# PWM_Output.net
KiCad netlist of a schematic drawn in Altium Designer
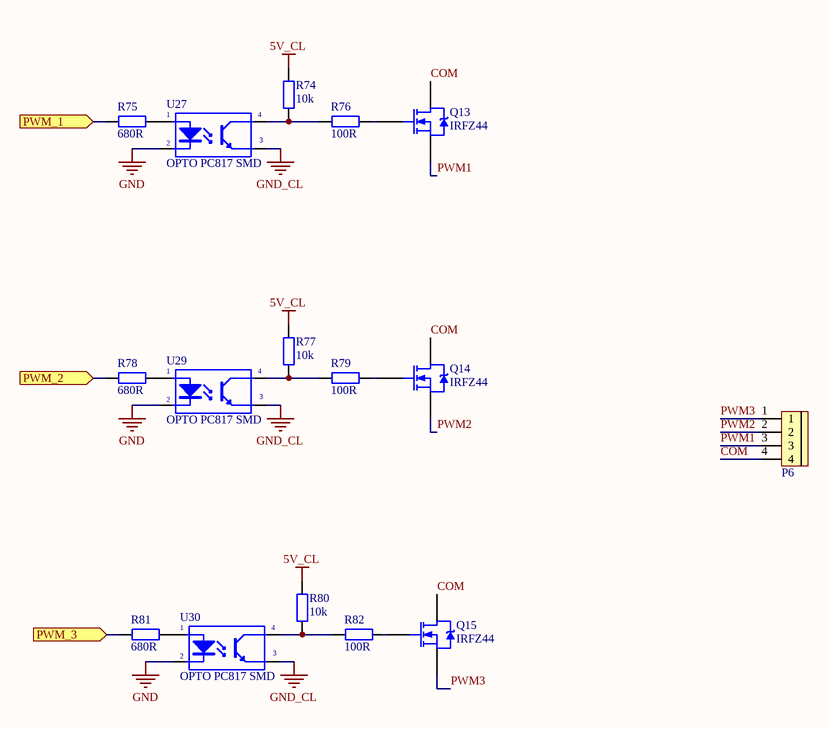
[diagram p0: PWM_Output.SchDoc]

(export (version "E")
  (design (tool "Eeschema 10.0.6"))
  (components
    (comp (ref "P6")
      (value "CON 4 EDG5.08")
      (footprint "CON 4 4EDG5.08")
      (description "Cắm")
      (libsource (lib "Altium_Lib_by_KhueNguyenCreator") (part "CON 4 EDG5.08"))
    )
    (comp (ref "Q13")
      (value "IRFZ44")
      (footprint "TO220")
      (description "N-Channel Power MOSFET")
      (libsource (lib "Altium_Lib_by_KhueNguyenCreator") (part "IRFZ44 DIP"))
    )
    (comp (ref "Q14")
      (value "IRFZ44")
      (footprint "TO220")
      (description "N-Channel Power MOSFET")
      (libsource (lib "Altium_Lib_by_KhueNguyenCreator") (part "IRFZ44 DIP"))
    )
    (comp (ref "Q15")
      (value "IRFZ44")
      (footprint "TO220")
      (description "N-Channel Power MOSFET")
      (libsource (lib "Altium_Lib_by_KhueNguyenCreator") (part "IRFZ44 DIP"))
    )
    (comp (ref "R74")
      (value "10k")
      (footprint "tro smd 0805")
      (description "Dán")
      (libsource (lib "Altium_Lib_by_KhueNguyenCreator") (part "Tro 0805 1% 10k"))
    )
    (comp (ref "R75")
      (value "680R")
      (footprint "tro smd 0805")
      (description "Dán")
      (libsource (lib "Altium_Lib_by_KhueNguyenCreator") (part "Tro 0805 1% 680R"))
    )
    (comp (ref "R76")
      (value "100R")
      (footprint "tro smd 0805")
      (description "Dán")
      (libsource (lib "Altium_Lib_by_KhueNguyenCreator") (part "Tro 0805 5% 100R"))
    )
    (comp (ref "R77")
      (value "10k")
      (footprint "tro smd 0805")
      (description "Dán")
      (libsource (lib "Altium_Lib_by_KhueNguyenCreator") (part "Tro 0805 1% 10k"))
    )
    (comp (ref "R78")
      (value "680R")
      (footprint "tro smd 0805")
      (description "Dán")
      (libsource (lib "Altium_Lib_by_KhueNguyenCreator") (part "Tro 0805 1% 680R"))
    )
    (comp (ref "R79")
      (value "100R")
      (footprint "tro smd 0805")
      (description "Dán")
      (libsource (lib "Altium_Lib_by_KhueNguyenCreator") (part "Tro 0805 5% 100R"))
    )
    (comp (ref "R80")
      (value "10k")
      (footprint "tro smd 0805")
      (description "Dán")
      (libsource (lib "Altium_Lib_by_KhueNguyenCreator") (part "Tro 0805 1% 10k"))
    )
    (comp (ref "R81")
      (value "680R")
      (footprint "tro smd 0805")
      (description "Dán")
      (libsource (lib "Altium_Lib_by_KhueNguyenCreator") (part "Tro 0805 1% 680R"))
    )
    (comp (ref "R82")
      (value "100R")
      (footprint "tro smd 0805")
      (description "Dán")
      (libsource (lib "Altium_Lib_by_KhueNguyenCreator") (part "Tro 0805 5% 100R"))
    )
    (comp (ref "U27")
      (value "OPTO PC817 SMD")
      (footprint "SOP4")
      (description "Single Opto")
      (libsource (lib "Altium_Lib_by_KhueNguyenCreator") (part "OPTO PC817 SMD"))
    )
    (comp (ref "U29")
      (value "OPTO PC817 SMD")
      (footprint "SOP4")
      (description "Single Opto")
      (libsource (lib "Altium_Lib_by_KhueNguyenCreator") (part "OPTO PC817 SMD"))
    )
    (comp (ref "U30")
      (value "OPTO PC817 SMD")
      (footprint "SOP4")
      (description "Single Opto")
      (libsource (lib "Altium_Lib_by_KhueNguyenCreator") (part "OPTO PC817 SMD"))
    )
  )
  (nets
    (net (code "1") (name "/COM") (class "Default")
      (node (ref "P6") (pin "4") (pinfunction "4_4") (pintype "passive"))
      (node (ref "Q13") (pin "2") (pinfunction "D_2") (pintype "passive"))
      (node (ref "Q14") (pin "2") (pinfunction "D_2") (pintype "passive"))
      (node (ref "Q15") (pin "2") (pinfunction "D_2") (pintype "passive"))
    )
    (net (code "2") (name "/PWM1") (class "Default")
      (node (ref "P6") (pin "3") (pinfunction "3_3") (pintype "passive"))
      (node (ref "Q13") (pin "3") (pinfunction "S_3") (pintype "passive"))
    )
    (net (code "3") (name "/PWM2") (class "Default")
      (node (ref "P6") (pin "2") (pinfunction "2_2") (pintype "passive"))
      (node (ref "Q14") (pin "3") (pinfunction "S_3") (pintype "passive"))
    )
    (net (code "4") (name "/PWM3") (class "Default")
      (node (ref "P6") (pin "1") (pinfunction "1_1") (pintype "passive"))
      (node (ref "Q15") (pin "3") (pinfunction "S_3") (pintype "passive"))
    )
    (net (code "5") (name "/PWM_1") (class "Default")
      (node (ref "R75") (pin "1") (pinfunction "1_1") (pintype "passive"))
    )
    (net (code "6") (name "/PWM_2") (class "Default")
      (node (ref "R78") (pin "1") (pinfunction "1_1") (pintype "passive"))
    )
    (net (code "7") (name "/PWM_3") (class "Default")
      (node (ref "R81") (pin "1") (pinfunction "1_1") (pintype "passive"))
    )
    (net (code "8") (name "5V_CL") (class "Default")
      (node (ref "R74") (pin "1") (pinfunction "1_1") (pintype "passive"))
      (node (ref "R77") (pin "1") (pinfunction "1_1") (pintype "passive"))
      (node (ref "R80") (pin "1") (pinfunction "1_1") (pintype "passive"))
    )
    (net (code "9") (name "GND") (class "Default")
      (node (ref "U27") (pin "2") (pinfunction "K_2") (pintype "passive"))
      (node (ref "U29") (pin "2") (pinfunction "K_2") (pintype "passive"))
      (node (ref "U30") (pin "2") (pinfunction "K_2") (pintype "passive"))
    )
    (net (code "10") (name "GND_CL") (class "Default")
      (node (ref "U27") (pin "3") (pinfunction "E_3") (pintype "passive"))
      (node (ref "U29") (pin "3") (pinfunction "E_3") (pintype "passive"))
      (node (ref "U30") (pin "3") (pinfunction "E_3") (pintype "passive"))
    )
    (net (code "11") (name "Net-(Q13-G)") (class "Default")
      (node (ref "Q13") (pin "1") (pinfunction "G_1") (pintype "passive"))
      (node (ref "R76") (pin "2") (pinfunction "2_2") (pintype "passive"))
    )
    (net (code "12") (name "Net-(Q14-G)") (class "Default")
      (node (ref "Q14") (pin "1") (pinfunction "G_1") (pintype "passive"))
      (node (ref "R79") (pin "2") (pinfunction "2_2") (pintype "passive"))
    )
    (net (code "13") (name "Net-(Q15-G)") (class "Default")
      (node (ref "Q15") (pin "1") (pinfunction "G_1") (pintype "passive"))
      (node (ref "R82") (pin "2") (pinfunction "2_2") (pintype "passive"))
    )
    (net (code "14") (name "Net-(U27-A)") (class "Default")
      (node (ref "R75") (pin "2") (pinfunction "2_2") (pintype "passive"))
      (node (ref "U27") (pin "1") (pinfunction "A_1") (pintype "passive"))
    )
    (net (code "15") (name "Net-(U27-C)") (class "Default")
      (node (ref "R74") (pin "2") (pinfunction "2_2") (pintype "passive"))
      (node (ref "R76") (pin "1") (pinfunction "1_1") (pintype "passive"))
      (node (ref "U27") (pin "4") (pinfunction "C_4") (pintype "passive"))
    )
    (net (code "16") (name "Net-(U29-A)") (class "Default")
      (node (ref "R78") (pin "2") (pinfunction "2_2") (pintype "passive"))
      (node (ref "U29") (pin "1") (pinfunction "A_1") (pintype "passive"))
    )
    (net (code "17") (name "Net-(U29-C)") (class "Default")
      (node (ref "R77") (pin "2") (pinfunction "2_2") (pintype "passive"))
      (node (ref "R79") (pin "1") (pinfunction "1_1") (pintype "passive"))
      (node (ref "U29") (pin "4") (pinfunction "C_4") (pintype "passive"))
    )
    (net (code "18") (name "Net-(U30-A)") (class "Default")
      (node (ref "R81") (pin "2") (pinfunction "2_2") (pintype "passive"))
      (node (ref "U30") (pin "1") (pinfunction "A_1") (pintype "passive"))
    )
    (net (code "19") (name "Net-(U30-C)") (class "Default")
      (node (ref "R80") (pin "2") (pinfunction "2_2") (pintype "passive"))
      (node (ref "R82") (pin "1") (pinfunction "1_1") (pintype "passive"))
      (node (ref "U30") (pin "4") (pinfunction "C_4") (pintype "passive"))
    )
  )
)
